# 1-Schematic_NRF52832_Touch_Switch_1ch.net
KiCad netlist of a schematic drawn in EasyEDA
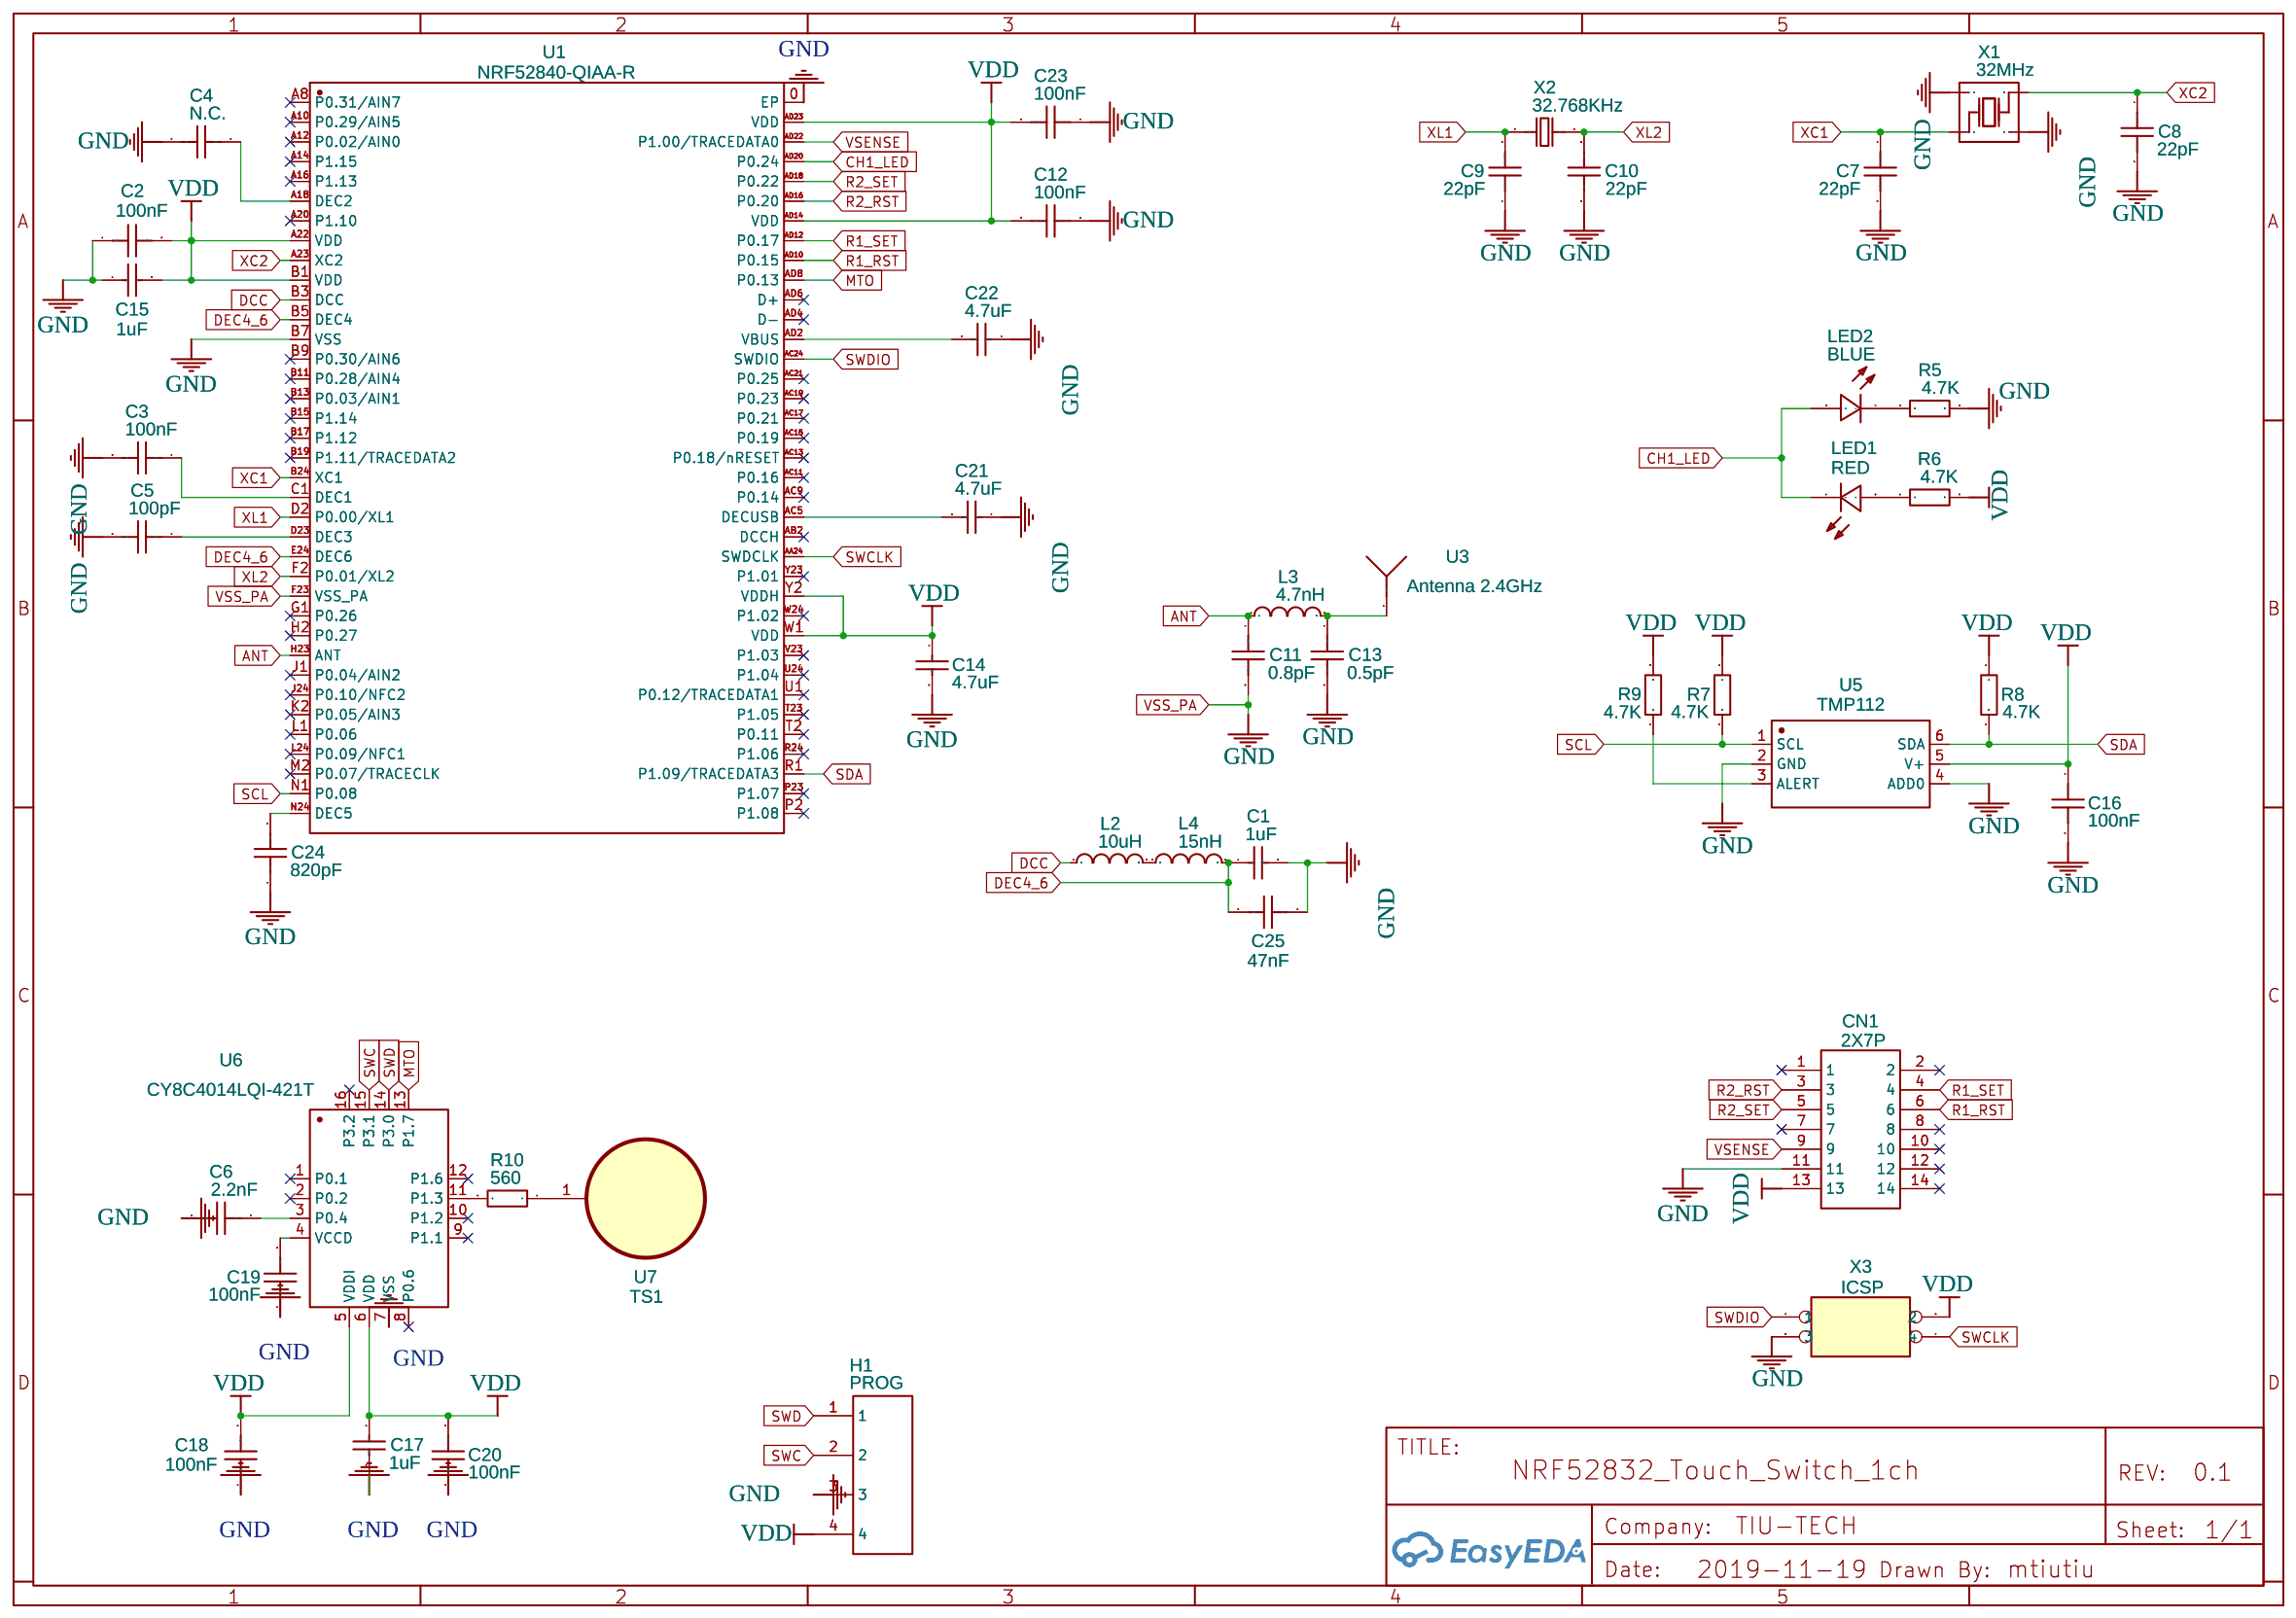
[diagram p0: schematic sheet]

(export (version "E")
  (design (tool "Eeschema 10.0.6"))
  (components
    (comp (ref "C1")
      (value "1uF")
      (fields
        (field (name "BOM_Manufacturer Part") "CL10B105KO8NNNC")
        (field (name "BOM_Supplier Part") "C59782")
      )
      (libsource (lib "") (part "CL10B105KO8NNNC_1"))
    )
    (comp (ref "C2")
      (value "100nF")
      (fields
        (field (name "BOM_Manufacturer Part") "C0603X104K050T")
        (field (name "BOM_Supplier Part") "C187860")
      )
      (libsource (lib "") (part "C0603X104K050T"))
    )
    (comp (ref "C3")
      (value "100nF")
      (fields
        (field (name "BOM_Manufacturer Part") "C0603X104K050T")
        (field (name "BOM_Supplier Part") "C187860")
      )
      (libsource (lib "") (part "C0603X104K050T_2"))
    )
    (comp (ref "C4")
      (value "N.C.")
      (fields
        (field (name "BOM_Manufacturer Part") "TCC0603COG101J500CT")
        (field (name "BOM_Supplier Part") "C344186")
      )
      (libsource (lib "") (part "TCC0603COG101J500CT"))
    )
    (comp (ref "C5")
      (value "100pF")
      (fields
        (field (name "BOM_Manufacturer Part") "TCC0603COG101J500CT")
        (field (name "BOM_Supplier Part") "C344186")
      )
      (libsource (lib "") (part "TCC0603COG101J500CT_1"))
    )
    (comp (ref "C6")
      (value "2.2nF")
      (fields
        (field (name "BOM_Manufacturer Part") "C0603X104K050T")
        (field (name "BOM_Supplier Part") "C187860")
      )
      (libsource (lib "") (part "C0603X104K050T_1"))
    )
    (comp (ref "C7")
      (value "22pF")
      (fields
        (field (name "BOM_Manufacturer Part") "0603N220J101")
        (field (name "BOM_Supplier Part") "C152915")
      )
      (libsource (lib "") (part "0603N220J101_1"))
    )
    (comp (ref "C8")
      (value "22pF")
      (fields
        (field (name "BOM_Manufacturer Part") "0603N220J101")
        (field (name "BOM_Supplier Part") "C152915")
      )
      (libsource (lib "") (part "0603N220J101_2"))
    )
    (comp (ref "C9")
      (value "22pF")
      (fields
        (field (name "BOM_Manufacturer Part") "0603N220J101")
        (field (name "BOM_Supplier Part") "C152915")
      )
      (libsource (lib "") (part "0603N220J101"))
    )
    (comp (ref "C10")
      (value "22pF")
      (fields
        (field (name "BOM_Manufacturer Part") "0603N220J101")
        (field (name "BOM_Supplier Part") "C152915")
      )
      (libsource (lib "") (part "0603N220J101"))
    )
    (comp (ref "C11")
      (value "0.8pF")
      (fields
        (field (name "BOM_Manufacturer Part") "CL05C0R5CB5NNNC")
        (field (name "BOM_Supplier Part") "C86284")
      )
      (libsource (lib "") (part "CL05C0R5CB5NNNC"))
    )
    (comp (ref "C12")
      (value "100nF")
      (fields
        (field (name "BOM_Manufacturer Part") "C0603X104K050T")
        (field (name "BOM_Supplier Part") "C187860")
      )
      (libsource (lib "") (part "C0603X104K050T_2"))
    )
    (comp (ref "C13")
      (value "0.5pF")
      (fields
        (field (name "BOM_Manufacturer Part") "CL05C0R5CB5NNNC")
        (field (name "BOM_Supplier Part") "C86284")
      )
      (libsource (lib "") (part "CL05C0R5CB5NNNC"))
    )
    (comp (ref "C14")
      (value "4.7uF")
      (fields
        (field (name "BOM_Manufacturer Part") "CL10A475KQ8NNNC")
        (field (name "BOM_Supplier Part") "C8032")
      )
      (libsource (lib "") (part "CL10A475KQ8NNNC_1"))
    )
    (comp (ref "C15")
      (value "1uF")
      (fields
        (field (name "BOM_Manufacturer Part") "CL10B105KO8NNNC")
        (field (name "BOM_Supplier Part") "C59782")
      )
      (libsource (lib "") (part "CL10B105KO8NNNC_2"))
    )
    (comp (ref "C16")
      (value "100nF")
      (fields
        (field (name "BOM_Manufacturer Part") "C0603X104K050T")
        (field (name "BOM_Supplier Part") "C187860")
      )
      (libsource (lib "") (part "C0603X104K050T_5"))
    )
    (comp (ref "C17")
      (value "1uF")
      (fields
        (field (name "BOM_Manufacturer Part") "CL10B105KO8NNNC")
        (field (name "BOM_Supplier Part") "C59782")
      )
      (libsource (lib "") (part "CL10B105KO8NNNC"))
    )
    (comp (ref "C18")
      (value "100nF")
      (fields
        (field (name "BOM_Manufacturer Part") "C0603X104K050T")
        (field (name "BOM_Supplier Part") "C187860")
      )
      (libsource (lib "") (part "C0603X104K050T_4"))
    )
    (comp (ref "C19")
      (value "100nF")
      (fields
        (field (name "BOM_Manufacturer Part") "C0603X104K050T")
        (field (name "BOM_Supplier Part") "C187860")
      )
      (libsource (lib "") (part "C0603X104K050T_3"))
    )
    (comp (ref "C20")
      (value "100nF")
      (fields
        (field (name "BOM_Manufacturer Part") "C0603X104K050T")
        (field (name "BOM_Supplier Part") "C187860")
      )
      (libsource (lib "") (part "C0603X104K050T_3"))
    )
    (comp (ref "C21")
      (value "4.7uF")
      (fields
        (field (name "BOM_Manufacturer Part") "CL10A475KQ8NNNC")
        (field (name "BOM_Supplier Part") "C8032")
      )
      (libsource (lib "") (part "CL10A475KQ8NNNC"))
    )
    (comp (ref "C22")
      (value "4.7uF")
      (fields
        (field (name "BOM_Manufacturer Part") "CL10A475KQ8NNNC")
        (field (name "BOM_Supplier Part") "C8032")
      )
      (libsource (lib "") (part "CL10A475KQ8NNNC"))
    )
    (comp (ref "C23")
      (value "100nF")
      (fields
        (field (name "BOM_Manufacturer Part") "C0603X104K050T")
        (field (name "BOM_Supplier Part") "C187860")
      )
      (libsource (lib "") (part "C0603X104K050T_2"))
    )
    (comp (ref "C24")
      (value "820pF")
      (fields
        (field (name "BOM_Manufacturer Part") "0603CG821J500NT")
        (field (name "BOM_Supplier Part") "C99081")
      )
      (libsource (lib "") (part "0603CG821J500NT"))
    )
    (comp (ref "C25")
      (value "47nF")
      (fields
        (field (name "BOM_Manufacturer Part") "GRM188B11C473KA01D")
        (field (name "BOM_Supplier Part") "C464442")
      )
      (libsource (lib "") (part "GRM188B11C473KA01D"))
    )
    (comp (ref "CN1")
      (value "2X7P")
      (fields
        (field (name "BOM_Manufacturer Part") "A2005HWV-2x7P")
        (field (name "BOM_Supplier Part") "C225306")
      )
      (libsource (lib "") (part "Unknown_935_565"))
    )
    (comp (ref "H1")
      (value "PROG")
      (fields (field (name "BOM_Manufacturer Part") "2x3 Header 1.27mm SMD"))
      (libsource (lib "") (part "1x4_Header_1.27mm_SMD"))
    )
    (comp (ref "L2")
      (value "10uH")
      (fields
        (field (name "BOM_Manufacturer Part") "MLZ1608M100WT000")
        (field (name "BOM_Supplier Part") "C76798")
      )
      (libsource (lib "") (part "MLZ1608M100WT000"))
    )
    (comp (ref "L3")
      (value "4.7nH")
      (fields
        (field (name "BOM_Manufacturer Part") "VHF160808H3N3ST")
        (field (name "BOM_Supplier Part") "C1029")
      )
      (libsource (lib "") (part "VHF160808H3N3ST"))
    )
    (comp (ref "L4")
      (value "15nH")
      (fields
        (field (name "BOM_Manufacturer Part") "SDCL1005C15NJTDF")
        (field (name "BOM_Supplier Part") "C27143")
      )
      (libsource (lib "") (part "SDCL1005C15NJTDF"))
    )
    (comp (ref "LED1")
      (value "RED")
      (fields
        (field (name "BOM_Manufacturer Part") "MHT192UBCT")
        (field (name "BOM_Supplier Part") "C389520")
      )
      (libsource (lib "") (part "Unknown_930_245"))
    )
    (comp (ref "LED2")
      (value "BLUE")
      (fields
        (field (name "BOM_Manufacturer Part") "MHT192UBCT")
        (field (name "BOM_Supplier Part") "C389520")
      )
      (libsource (lib "") (part "Unknown_930_200"))
    )
    (comp (ref "R5")
      (value "4.7K")
      (fields
        (field (name "BOM_Manufacturer Part") "RMC06034.7k5%N")
        (field (name "BOM_Supplier Part") "C269694")
      )
      (libsource (lib "") (part "RMC06034.7K5%N_1"))
    )
    (comp (ref "R6")
      (value "4.7K")
      (fields
        (field (name "BOM_Manufacturer Part") "RMC06034.7k5%N")
        (field (name "BOM_Supplier Part") "C269694")
      )
      (libsource (lib "") (part "RMC06034.7K5%N_1"))
    )
    (comp (ref "R7")
      (value "4.7K")
      (fields
        (field (name "BOM_Manufacturer Part") "RMC06034.7k5%N")
        (field (name "BOM_Supplier Part") "C269694")
      )
      (libsource (lib "") (part "RMC06034.7K5%N_2"))
    )
    (comp (ref "R8")
      (value "4.7K")
      (fields
        (field (name "BOM_Manufacturer Part") "RMC06034.7k5%N")
        (field (name "BOM_Supplier Part") "C269694")
      )
      (libsource (lib "") (part "RMC06034.7K5%N_2"))
    )
    (comp (ref "R9")
      (value "4.7K")
      (fields
        (field (name "BOM_Manufacturer Part") "RMC06034.7k5%N")
        (field (name "BOM_Supplier Part") "C269694")
      )
      (libsource (lib "") (part "RMC06034.7K5%N"))
    )
    (comp (ref "R10")
      (value "560")
      (fields
        (field (name "BOM_Manufacturer Part") "RMC06034.7k5%N")
        (field (name "BOM_Supplier Part") "C269694")
      )
      (libsource (lib "") (part "RMC06034.7K5%N_3"))
    )
    (comp (ref "U1")
      (value "NRF52840-QIAA-R")
      (fields (field (name "BOM_Supplier Part") "C190794"))
      (libsource (lib "") (part "NRF52840-QIAA-R"))
    )
    (comp (ref "U3")
      (value "Antenna 2.4GHz")
      (fields (field (name "BOM_Manufacturer Part") "AN6520") (field (name "BOM_Supplier Part") "C239238"))
      (libsource (lib "") (part "Unknown_695_285"))
    )
    (comp (ref "U5")
      (value "TMP112")
      (fields
        (field (name "BOM_Manufacturer Part") "TMP112AIDRLR")
        (field (name "BOM_Supplier Part") "C28927")
      )
      (libsource (lib "") (part "TMP112AIDRLR"))
    )
    (comp (ref "U6") (value "CY8C4014LQI-421T") (libsource (lib "") (part "CY8C4014LQI-421T")))
    (comp (ref "U7") (value "TS1") (libsource (lib "") (part "Unknown_320_600")))
    (comp (ref "X1")
      (value "32MHz")
      (fields
        (field (name "BOM_Manufacturer Part") "7216-3200A1210-00")
        (field (name "BOM_Supplier Part") "C389799")
      )
      (libsource (lib "") (part "7216-3200A1210-00"))
    )
    (comp (ref "X2")
      (value "32.768KHz")
      (fields
        (field (name "BOM_Manufacturer Part") "Q13FC1350000400")
        (field (name "BOM_Supplier Part") "C32346")
      )
      (libsource (lib "") (part "Q13FC1350000400"))
    )
    (comp (ref "X3") (value "ICSP") (libsource (lib "") (part "Unknown_935_670")))
  )
  (nets
    (net (code "1") (name "ANT") (class "Default")
      (node (ref "C11") (pin "1") (pinfunction "1_1") (pintype "unspecified"))
      (node (ref "L3") (pin "1") (pinfunction "1_1") (pintype "unspecified"))
      (node (ref "U1") (pin "H23") (pinfunction "ANT_H23") (pintype "unspecified"))
    )
    (net (code "2") (name "CH1_LED") (class "Default")
      (node (ref "LED1") (pin "1") (pinfunction "-_1") (pintype "unspecified"))
      (node (ref "LED2") (pin "2") (pinfunction "+_2") (pintype "unspecified"))
      (node (ref "U1") (pin "AD20") (pinfunction "P0.24_AD20") (pintype "unspecified"))
    )
    (net (code "3") (name "DCC") (class "Default")
      (node (ref "L2") (pin "1") (pinfunction "1_1") (pintype "unspecified"))
      (node (ref "U1") (pin "B3") (pinfunction "DCC_B3") (pintype "unspecified"))
    )
    (net (code "4") (name "DEC4_6") (class "Default")
      (node (ref "C1") (pin "1") (pinfunction "1_1") (pintype "input"))
      (node (ref "C25") (pin "2") (pinfunction "2_2") (pintype "unspecified"))
      (node (ref "L4") (pin "2") (pinfunction "2_2") (pintype "unspecified"))
      (node (ref "U1") (pin "B5") (pinfunction "DEC4_B5") (pintype "unspecified"))
      (node (ref "U1") (pin "E24") (pinfunction "DEC6_E24") (pintype "unspecified"))
    )
    (net (code "5") (name "MTO") (class "Default")
      (node (ref "U1") (pin "AD8") (pinfunction "P0.13_AD8") (pintype "unspecified"))
      (node (ref "U6") (pin "13") (pinfunction "P1.7_13") (pintype "unspecified"))
    )
    (net (code "6") (name "Net-(C13-Pad1)") (class "Default")
      (node (ref "C13") (pin "1") (pinfunction "1_1") (pintype "unspecified"))
      (node (ref "L3") (pin "2") (pinfunction "2_2") (pintype "unspecified"))
      (node (ref "U3") (pin "1") (pinfunction "1_1") (pintype "unspecified"))
    )
    (net (code "7") (name "Net-(L2-Pad2)") (class "Default")
      (node (ref "L2") (pin "2") (pinfunction "2_2") (pintype "unspecified"))
      (node (ref "L4") (pin "1") (pinfunction "1_1") (pintype "unspecified"))
    )
    (net (code "8") (name "Net-(LED1-+)") (class "Default")
      (node (ref "LED1") (pin "2") (pinfunction "+_2") (pintype "unspecified"))
      (node (ref "R6") (pin "1") (pinfunction "1_1") (pintype "unspecified"))
    )
    (net (code "9") (name "Net-(LED2--)") (class "Default")
      (node (ref "LED2") (pin "1") (pinfunction "-_1") (pintype "unspecified"))
      (node (ref "R5") (pin "1") (pinfunction "1_1") (pintype "unspecified"))
    )
    (net (code "10") (name "Net-(R10-Pad1)") (class "Default")
      (node (ref "R10") (pin "1") (pinfunction "1_1") (pintype "unspecified"))
      (node (ref "U7") (pin "1") (pintype "unspecified"))
    )
    (net (code "11") (name "Net-(U1-DEC1)") (class "Default")
      (node (ref "C3") (pin "1") (pinfunction "1_1") (pintype "unspecified"))
      (node (ref "U1") (pin "C1") (pinfunction "DEC1_C1") (pintype "unspecified"))
    )
    (net (code "12") (name "Net-(U1-DEC2)") (class "Default")
      (node (ref "C4") (pin "2") (pinfunction "2_2") (pintype "unspecified"))
      (node (ref "U1") (pin "A18") (pinfunction "DEC2_A18") (pintype "unspecified"))
    )
    (net (code "13") (name "Net-(U1-DEC3)") (class "Default")
      (node (ref "C5") (pin "1") (pinfunction "1_1") (pintype "unspecified"))
      (node (ref "U1") (pin "D23") (pinfunction "DEC3_D23") (pintype "unspecified"))
    )
    (net (code "14") (name "Net-(U1-DEC5)") (class "Default")
      (node (ref "C24") (pin "2") (pinfunction "2_2") (pintype "unspecified"))
      (node (ref "U1") (pin "N24") (pinfunction "DEC5_N24") (pintype "unspecified"))
    )
    (net (code "15") (name "Net-(U1-DECUSB)") (class "Default")
      (node (ref "C21") (pin "2") (pinfunction "2_2") (pintype "input"))
      (node (ref "U1") (pin "AC5") (pinfunction "DECUSB_AC5") (pintype "unspecified"))
    )
    (net (code "16") (name "Net-(U1-VBUS)") (class "Default")
      (node (ref "C22") (pin "2") (pinfunction "2_2") (pintype "input"))
      (node (ref "U1") (pin "AD2") (pinfunction "VBUS_AD2") (pintype "unspecified"))
    )
    (net (code "17") (name "Net-(U5-ALERT)") (class "Default")
      (node (ref "R9") (pin "1") (pinfunction "1_1") (pintype "unspecified"))
      (node (ref "U5") (pin "3") (pinfunction "ALERT_3") (pintype "unspecified"))
    )
    (net (code "18") (name "Net-(U6-P0.4)") (class "Default")
      (node (ref "C6") (pin "1") (pinfunction "1_1") (pintype "unspecified"))
      (node (ref "U6") (pin "3") (pinfunction "P0.4_3") (pintype "unspecified"))
    )
    (net (code "19") (name "Net-(U6-P1.3)") (class "Default")
      (node (ref "R10") (pin "2") (pinfunction "2_2") (pintype "unspecified"))
      (node (ref "U6") (pin "11") (pinfunction "P1.3_11") (pintype "unspecified"))
    )
    (net (code "20") (name "Net-(U6-VCCD)") (class "Default")
      (node (ref "C19") (pin "2") (pinfunction "2_2") (pintype "unspecified"))
      (node (ref "U6") (pin "4") (pinfunction "VCCD_4") (pintype "unspecified"))
    )
    (net (code "21") (name "R1_RST") (class "Default")
      (node (ref "CN1") (pin "6") (pinfunction "6_6") (pintype "unspecified"))
      (node (ref "U1") (pin "AD10") (pinfunction "P0.15_AD10") (pintype "unspecified"))
    )
    (net (code "22") (name "R1_SET") (class "Default")
      (node (ref "CN1") (pin "4") (pinfunction "4_4") (pintype "unspecified"))
      (node (ref "U1") (pin "AD12") (pinfunction "P0.17_AD12") (pintype "unspecified"))
    )
    (net (code "23") (name "R2_RST") (class "Default")
      (node (ref "CN1") (pin "3") (pinfunction "3_3") (pintype "unspecified"))
      (node (ref "U1") (pin "AD16") (pinfunction "P0.20_AD16") (pintype "unspecified"))
    )
    (net (code "24") (name "R2_SET") (class "Default")
      (node (ref "CN1") (pin "5") (pinfunction "5_5") (pintype "unspecified"))
      (node (ref "U1") (pin "AD18") (pinfunction "P0.22_AD18") (pintype "unspecified"))
    )
    (net (code "25") (name "SCL") (class "Default")
      (node (ref "R7") (pin "2") (pinfunction "2_2") (pintype "unspecified"))
      (node (ref "U1") (pin "N1") (pinfunction "P0.08_N1") (pintype "unspecified"))
      (node (ref "U5") (pin "1") (pinfunction "SCL_1") (pintype "unspecified"))
    )
    (net (code "26") (name "SDA") (class "Default")
      (node (ref "R8") (pin "2") (pinfunction "2_2") (pintype "unspecified"))
      (node (ref "U1") (pin "R1") (pinfunction "P1.09/TRACEDATA3_R1") (pintype "unspecified"))
      (node (ref "U5") (pin "6") (pinfunction "SDA_6") (pintype "unspecified"))
    )
    (net (code "27") (name "SWC") (class "Default")
      (node (ref "H1") (pin "2") (pinfunction "2_2") (pintype "unspecified"))
      (node (ref "U6") (pin "15") (pinfunction "P3.1_15") (pintype "unspecified"))
    )
    (net (code "28") (name "SWCLK") (class "Default")
      (node (ref "U1") (pin "AA24") (pinfunction "SWDCLK_AA24") (pintype "unspecified"))
      (node (ref "X3") (pin "4") (pinfunction "4_4") (pintype "unspecified"))
    )
    (net (code "29") (name "SWD") (class "Default")
      (node (ref "H1") (pin "1") (pinfunction "1_1") (pintype "unspecified"))
      (node (ref "U6") (pin "14") (pinfunction "P3.0_14") (pintype "unspecified"))
    )
    (net (code "30") (name "SWDIO") (class "Default")
      (node (ref "U1") (pin "AC24") (pinfunction "SWDIO_AC24") (pintype "unspecified"))
      (node (ref "X3") (pin "1") (pinfunction "1_1") (pintype "unspecified"))
    )
    (net (code "31") (name "VDD") (class "Default")
      (node (ref "C12") (pin "2") (pinfunction "2_2") (pintype "unspecified"))
      (node (ref "C14") (pin "1") (pinfunction "1_1") (pintype "input"))
      (node (ref "C15") (pin "2") (pinfunction "2_2") (pintype "input"))
      (node (ref "C16") (pin "1") (pinfunction "1_1") (pintype "unspecified"))
      (node (ref "C17") (pin "2") (pinfunction "2_2") (pintype "input"))
      (node (ref "C18") (pin "2") (pinfunction "2_2") (pintype "unspecified"))
      (node (ref "C2") (pin "2") (pinfunction "2_2") (pintype "unspecified"))
      (node (ref "C20") (pin "2") (pinfunction "2_2") (pintype "unspecified"))
      (node (ref "C23") (pin "2") (pinfunction "2_2") (pintype "unspecified"))
      (node (ref "CN1") (pin "13") (pinfunction "13_13") (pintype "unspecified"))
      (node (ref "H1") (pin "4") (pinfunction "4_4") (pintype "unspecified"))
      (node (ref "R6") (pin "2") (pinfunction "2_2") (pintype "unspecified"))
      (node (ref "R7") (pin "1") (pinfunction "1_1") (pintype "unspecified"))
      (node (ref "R8") (pin "1") (pinfunction "1_1") (pintype "unspecified"))
      (node (ref "R9") (pin "2") (pinfunction "2_2") (pintype "unspecified"))
      (node (ref "U1") (pin "A22") (pinfunction "VDD_A22") (pintype "unspecified"))
      (node (ref "U1") (pin "AD14") (pinfunction "VDD_AD14") (pintype "unspecified"))
      (node (ref "U1") (pin "AD23") (pinfunction "VDD_AD23") (pintype "unspecified"))
      (node (ref "U1") (pin "B1") (pinfunction "VDD_B1") (pintype "unspecified"))
      (node (ref "U1") (pin "W1") (pinfunction "VDD_W1") (pintype "unspecified"))
      (node (ref "U1") (pin "Y2") (pinfunction "VDDH_Y2") (pintype "unspecified"))
      (node (ref "U5") (pin "5") (pinfunction "V+_5") (pintype "unspecified"))
      (node (ref "U6") (pin "5") (pinfunction "VDDI_5") (pintype "unspecified"))
      (node (ref "U6") (pin "6") (pinfunction "VDD_6") (pintype "unspecified"))
      (node (ref "X3") (pin "2") (pinfunction "2_2") (pintype "unspecified"))
    )
    (net (code "32") (name "VSENSE") (class "Default")
      (node (ref "CN1") (pin "9") (pinfunction "9_9") (pintype "unspecified"))
      (node (ref "U1") (pin "AD22") (pinfunction "P1.00/TRACEDATA0_AD22") (pintype "unspecified"))
    )
    (net (code "33") (name "VSS_PA") (class "Default")
      (node (ref "C1") (pin "2") (pinfunction "2_2") (pintype "input"))
      (node (ref "C10") (pin "1") (pinfunction "1_1") (pintype "unspecified"))
      (node (ref "C11") (pin "2") (pinfunction "2_2") (pintype "unspecified"))
      (node (ref "C12") (pin "1") (pinfunction "1_1") (pintype "unspecified"))
      (node (ref "C13") (pin "2") (pinfunction "2_2") (pintype "unspecified"))
      (node (ref "C14") (pin "2") (pinfunction "2_2") (pintype "input"))
      (node (ref "C15") (pin "1") (pinfunction "1_1") (pintype "input"))
      (node (ref "C16") (pin "2") (pinfunction "2_2") (pintype "unspecified"))
      (node (ref "C17") (pin "1") (pinfunction "1_1") (pintype "input"))
      (node (ref "C18") (pin "1") (pinfunction "1_1") (pintype "unspecified"))
      (node (ref "C19") (pin "1") (pinfunction "1_1") (pintype "unspecified"))
      (node (ref "C2") (pin "1") (pinfunction "1_1") (pintype "unspecified"))
      (node (ref "C20") (pin "1") (pinfunction "1_1") (pintype "unspecified"))
      (node (ref "C21") (pin "1") (pinfunction "1_1") (pintype "input"))
      (node (ref "C22") (pin "1") (pinfunction "1_1") (pintype "input"))
      (node (ref "C23") (pin "1") (pinfunction "1_1") (pintype "unspecified"))
      (node (ref "C24") (pin "1") (pinfunction "1_1") (pintype "unspecified"))
      (node (ref "C25") (pin "1") (pinfunction "1_1") (pintype "unspecified"))
      (node (ref "C3") (pin "2") (pinfunction "2_2") (pintype "unspecified"))
      (node (ref "C4") (pin "1") (pinfunction "1_1") (pintype "unspecified"))
      (node (ref "C5") (pin "2") (pinfunction "2_2") (pintype "unspecified"))
      (node (ref "C6") (pin "2") (pinfunction "2_2") (pintype "unspecified"))
      (node (ref "C7") (pin "2") (pinfunction "2_2") (pintype "unspecified"))
      (node (ref "C8") (pin "2") (pinfunction "2_2") (pintype "unspecified"))
      (node (ref "C9") (pin "1") (pinfunction "1_1") (pintype "unspecified"))
      (node (ref "CN1") (pin "11") (pinfunction "11_11") (pintype "unspecified"))
      (node (ref "H1") (pin "3") (pinfunction "3_3") (pintype "unspecified"))
      (node (ref "R5") (pin "2") (pinfunction "2_2") (pintype "unspecified"))
      (node (ref "U1") (pin "0") (pinfunction "EP_0") (pintype "unspecified"))
      (node (ref "U1") (pin "B7") (pinfunction "VSS_B7") (pintype "unspecified"))
      (node (ref "U1") (pin "F23") (pinfunction "VSS_PA_F23") (pintype "unspecified"))
      (node (ref "U5") (pin "2") (pinfunction "GND_2") (pintype "unspecified"))
      (node (ref "U5") (pin "4") (pinfunction "ADD0_4") (pintype "unspecified"))
      (node (ref "U6") (pin "7") (pinfunction "VSS_7") (pintype "unspecified"))
      (node (ref "X1") (pin "2") (pinfunction "2_2") (pintype "input"))
      (node (ref "X1") (pin "4") (pinfunction "4_4") (pintype "input"))
      (node (ref "X3") (pin "3") (pinfunction "3_3") (pintype "unspecified"))
    )
    (net (code "34") (name "XC1") (class "Default")
      (node (ref "C7") (pin "1") (pinfunction "1_1") (pintype "unspecified"))
      (node (ref "U1") (pin "B24") (pinfunction "XC1_B24") (pintype "unspecified"))
      (node (ref "X1") (pin "1") (pinfunction "1_1") (pintype "input"))
    )
    (net (code "35") (name "XC2") (class "Default")
      (node (ref "C8") (pin "1") (pinfunction "1_1") (pintype "unspecified"))
      (node (ref "U1") (pin "A23") (pinfunction "XC2_A23") (pintype "unspecified"))
      (node (ref "X1") (pin "3") (pinfunction "3_3") (pintype "input"))
    )
    (net (code "36") (name "XL1") (class "Default")
      (node (ref "C9") (pin "2") (pinfunction "2_2") (pintype "unspecified"))
      (node (ref "U1") (pin "D2") (pinfunction "P0.00/XL1_D2") (pintype "unspecified"))
      (node (ref "X2") (pin "1") (pinfunction "1_1") (pintype "unspecified"))
    )
    (net (code "37") (name "XL2") (class "Default")
      (node (ref "C10") (pin "2") (pinfunction "2_2") (pintype "unspecified"))
      (node (ref "U1") (pin "F2") (pinfunction "P0.01/XL2_F2") (pintype "unspecified"))
      (node (ref "X2") (pin "2") (pinfunction "2_2") (pintype "unspecified"))
    )
    (net (code "38") (name "unconnected-(CN1-Pad1)") (class "Default")
      (node (ref "CN1") (pin "1") (pinfunction "1_1") (pintype "unspecified+no_connect"))
    )
    (net (code "39") (name "unconnected-(CN1-Pad2)") (class "Default")
      (node (ref "CN1") (pin "2") (pinfunction "2_2") (pintype "unspecified+no_connect"))
    )
    (net (code "40") (name "unconnected-(CN1-Pad7)") (class "Default")
      (node (ref "CN1") (pin "7") (pinfunction "7_7") (pintype "unspecified+no_connect"))
    )
    (net (code "41") (name "unconnected-(CN1-Pad8)") (class "Default")
      (node (ref "CN1") (pin "8") (pinfunction "8_8") (pintype "unspecified+no_connect"))
    )
    (net (code "42") (name "unconnected-(CN1-Pad10)") (class "Default")
      (node (ref "CN1") (pin "10") (pinfunction "10_10") (pintype "unspecified+no_connect"))
    )
    (net (code "43") (name "unconnected-(CN1-Pad12)") (class "Default")
      (node (ref "CN1") (pin "12") (pinfunction "12_12") (pintype "unspecified+no_connect"))
    )
    (net (code "44") (name "unconnected-(CN1-Pad14)") (class "Default")
      (node (ref "CN1") (pin "14") (pinfunction "14_14") (pintype "unspecified+no_connect"))
    )
    (net (code "45") (name "unconnected-(U1-D+-PadAD6)") (class "Default")
      (node (ref "U1") (pin "AD6") (pinfunction "D+_AD6") (pintype "unspecified+no_connect"))
    )
    (net (code "46") (name "unconnected-(U1-D--PadAD4)") (class "Default")
      (node (ref "U1") (pin "AD4") (pinfunction "D-_AD4") (pintype "unspecified+no_connect"))
    )
    (net (code "47") (name "unconnected-(U1-DCCH-PadAB2)") (class "Default")
      (node (ref "U1") (pin "AB2") (pinfunction "DCCH_AB2") (pintype "unspecified+no_connect"))
    )
    (net (code "48") (name "unconnected-(U1-P0.02{slash}AIN0-PadA12)") (class "Default")
      (node (ref "U1") (pin "A12") (pinfunction "P0.02/AIN0_A12") (pintype "unspecified+no_connect"))
    )
    (net (code "49") (name "unconnected-(U1-P0.03{slash}AIN1-PadB13)") (class "Default")
      (node (ref "U1") (pin "B13") (pinfunction "P0.03/AIN1_B13") (pintype "unspecified+no_connect"))
    )
    (net (code "50") (name "unconnected-(U1-P0.04{slash}AIN2-PadJ1)") (class "Default")
      (node (ref "U1") (pin "J1") (pinfunction "P0.04/AIN2_J1") (pintype "unspecified+no_connect"))
    )
    (net (code "51") (name "unconnected-(U1-P0.05{slash}AIN3-PadK2)") (class "Default")
      (node (ref "U1") (pin "K2") (pinfunction "P0.05/AIN3_K2") (pintype "unspecified+no_connect"))
    )
    (net (code "52") (name "unconnected-(U1-P0.06-PadL1)") (class "Default")
      (node (ref "U1") (pin "L1") (pinfunction "P0.06_L1") (pintype "unspecified+no_connect"))
    )
    (net (code "53") (name "unconnected-(U1-P0.07{slash}TRACECLK-PadM2)") (class "Default")
      (node (ref "U1") (pin "M2") (pinfunction "P0.07/TRACECLK_M2") (pintype "unspecified+no_connect"))
    )
    (net (code "54") (name "unconnected-(U1-P0.09{slash}NFC1-PadL24)") (class "Default")
      (node (ref "U1") (pin "L24") (pinfunction "P0.09/NFC1_L24") (pintype "unspecified+no_connect"))
    )
    (net (code "55") (name "unconnected-(U1-P0.10{slash}NFC2-PadJ24)") (class "Default")
      (node (ref "U1") (pin "J24") (pinfunction "P0.10/NFC2_J24") (pintype "unspecified+no_connect"))
    )
    (net (code "56") (name "unconnected-(U1-P0.11-PadT2)") (class "Default")
      (node (ref "U1") (pin "T2") (pinfunction "P0.11_T2") (pintype "unspecified+no_connect"))
    )
    (net (code "57") (name "unconnected-(U1-P0.12{slash}TRACEDATA1-PadU1)") (class "Default")
      (node (ref "U1") (pin "U1") (pinfunction "P0.12/TRACEDATA1_U1") (pintype "unspecified+no_connect"))
    )
    (net (code "58") (name "unconnected-(U1-P0.14-PadAC9)") (class "Default")
      (node (ref "U1") (pin "AC9") (pinfunction "P0.14_AC9") (pintype "unspecified+no_connect"))
    )
    (net (code "59") (name "unconnected-(U1-P0.16-PadAC11)") (class "Default")
      (node (ref "U1") (pin "AC11") (pinfunction "P0.16_AC11") (pintype "unspecified+no_connect"))
    )
    (net (code "60") (name "unconnected-(U1-P0.18{slash}nRESET-PadAC13)") (class "Default")
      (node (ref "U1") (pin "AC13") (pinfunction "P0.18/nRESET_AC13") (pintype "unspecified+no_connect"))
    )
    (net (code "61") (name "unconnected-(U1-P0.19-PadAC15)") (class "Default")
      (node (ref "U1") (pin "AC15") (pinfunction "P0.19_AC15") (pintype "unspecified+no_connect"))
    )
    (net (code "62") (name "unconnected-(U1-P0.21-PadAC17)") (class "Default")
      (node (ref "U1") (pin "AC17") (pinfunction "P0.21_AC17") (pintype "unspecified+no_connect"))
    )
    (net (code "63") (name "unconnected-(U1-P0.23-PadAC19)") (class "Default")
      (node (ref "U1") (pin "AC19") (pinfunction "P0.23_AC19") (pintype "unspecified+no_connect"))
    )
    (net (code "64") (name "unconnected-(U1-P0.25-PadAC21)") (class "Default")
      (node (ref "U1") (pin "AC21") (pinfunction "P0.25_AC21") (pintype "unspecified+no_connect"))
    )
    (net (code "65") (name "unconnected-(U1-P0.26-PadG1)") (class "Default")
      (node (ref "U1") (pin "G1") (pinfunction "P0.26_G1") (pintype "unspecified+no_connect"))
    )
    (net (code "66") (name "unconnected-(U1-P0.27-PadH2)") (class "Default")
      (node (ref "U1") (pin "H2") (pinfunction "P0.27_H2") (pintype "unspecified+no_connect"))
    )
    (net (code "67") (name "unconnected-(U1-P0.28{slash}AIN4-PadB11)") (class "Default")
      (node (ref "U1") (pin "B11") (pinfunction "P0.28/AIN4_B11") (pintype "unspecified+no_connect"))
    )
    (net (code "68") (name "unconnected-(U1-P0.29{slash}AIN5-PadA10)") (class "Default")
      (node (ref "U1") (pin "A10") (pinfunction "P0.29/AIN5_A10") (pintype "unspecified+no_connect"))
    )
    (net (code "69") (name "unconnected-(U1-P0.30{slash}AIN6-PadB9)") (class "Default")
      (node (ref "U1") (pin "B9") (pinfunction "P0.30/AIN6_B9") (pintype "unspecified+no_connect"))
    )
    (net (code "70") (name "unconnected-(U1-P0.31{slash}AIN7-PadA8)") (class "Default")
      (node (ref "U1") (pin "A8") (pinfunction "P0.31/AIN7_A8") (pintype "unspecified+no_connect"))
    )
    (net (code "71") (name "unconnected-(U1-P1.01-PadY23)") (class "Default")
      (node (ref "U1") (pin "Y23") (pinfunction "P1.01_Y23") (pintype "unspecified+no_connect"))
    )
    (net (code "72") (name "unconnected-(U1-P1.02-PadW24)") (class "Default")
      (node (ref "U1") (pin "W24") (pinfunction "P1.02_W24") (pintype "unspecified+no_connect"))
    )
    (net (code "73") (name "unconnected-(U1-P1.03-PadV23)") (class "Default")
      (node (ref "U1") (pin "V23") (pinfunction "P1.03_V23") (pintype "unspecified+no_connect"))
    )
    (net (code "74") (name "unconnected-(U1-P1.04-PadU24)") (class "Default")
      (node (ref "U1") (pin "U24") (pinfunction "P1.04_U24") (pintype "unspecified+no_connect"))
    )
    (net (code "75") (name "unconnected-(U1-P1.05-PadT23)") (class "Default")
      (node (ref "U1") (pin "T23") (pinfunction "P1.05_T23") (pintype "unspecified+no_connect"))
    )
    (net (code "76") (name "unconnected-(U1-P1.06-PadR24)") (class "Default")
      (node (ref "U1") (pin "R24") (pinfunction "P1.06_R24") (pintype "unspecified+no_connect"))
    )
    (net (code "77") (name "unconnected-(U1-P1.07-PadP23)") (class "Default")
      (node (ref "U1") (pin "P23") (pinfunction "P1.07_P23") (pintype "unspecified+no_connect"))
    )
    (net (code "78") (name "unconnected-(U1-P1.08-PadP2)") (class "Default")
      (node (ref "U1") (pin "P2") (pinfunction "P1.08_P2") (pintype "unspecified+no_connect"))
    )
    (net (code "79") (name "unconnected-(U1-P1.10-PadA20)") (class "Default")
      (node (ref "U1") (pin "A20") (pinfunction "P1.10_A20") (pintype "unspecified+no_connect"))
    )
    (net (code "80") (name "unconnected-(U1-P1.11{slash}TRACEDATA2-PadB19)") (class "Default")
      (node (ref "U1") (pin "B19") (pinfunction "P1.11/TRACEDATA2_B19") (pintype "unspecified+no_connect"))
    )
    (net (code "81") (name "unconnected-(U1-P1.12-PadB17)") (class "Default")
      (node (ref "U1") (pin "B17") (pinfunction "P1.12_B17") (pintype "unspecified+no_connect"))
    )
    (net (code "82") (name "unconnected-(U1-P1.13-PadA16)") (class "Default")
      (node (ref "U1") (pin "A16") (pinfunction "P1.13_A16") (pintype "unspecified+no_connect"))
    )
    (net (code "83") (name "unconnected-(U1-P1.14-PadB15)") (class "Default")
      (node (ref "U1") (pin "B15") (pinfunction "P1.14_B15") (pintype "unspecified+no_connect"))
    )
    (net (code "84") (name "unconnected-(U1-P1.15-PadA14)") (class "Default")
      (node (ref "U1") (pin "A14") (pinfunction "P1.15_A14") (pintype "unspecified+no_connect"))
    )
    (net (code "85") (name "unconnected-(U6-P0.1-Pad1)") (class "Default")
      (node (ref "U6") (pin "1") (pinfunction "P0.1_1") (pintype "unspecified+no_connect"))
    )
    (net (code "86") (name "unconnected-(U6-P0.2-Pad2)") (class "Default")
      (node (ref "U6") (pin "2") (pinfunction "P0.2_2") (pintype "unspecified+no_connect"))
    )
    (net (code "87") (name "unconnected-(U6-P0.6-Pad8)") (class "Default")
      (node (ref "U6") (pin "8") (pinfunction "P0.6_8") (pintype "unspecified+no_connect"))
    )
    (net (code "88") (name "unconnected-(U6-P1.1-Pad9)") (class "Default")
      (node (ref "U6") (pin "9") (pinfunction "P1.1_9") (pintype "unspecified+no_connect"))
    )
    (net (code "89") (name "unconnected-(U6-P1.2-Pad10)") (class "Default")
      (node (ref "U6") (pin "10") (pinfunction "P1.2_10") (pintype "unspecified+no_connect"))
    )
    (net (code "90") (name "unconnected-(U6-P1.6-Pad12)") (class "Default")
      (node (ref "U6") (pin "12") (pinfunction "P1.6_12") (pintype "unspecified+no_connect"))
    )
    (net (code "91") (name "unconnected-(U6-P3.2-Pad16)") (class "Default")
      (node (ref "U6") (pin "16") (pinfunction "P3.2_16") (pintype "unspecified+no_connect"))
    )
  )
)
